# powerBoard.net
KiCad netlist of a schematic drawn in EAGLE
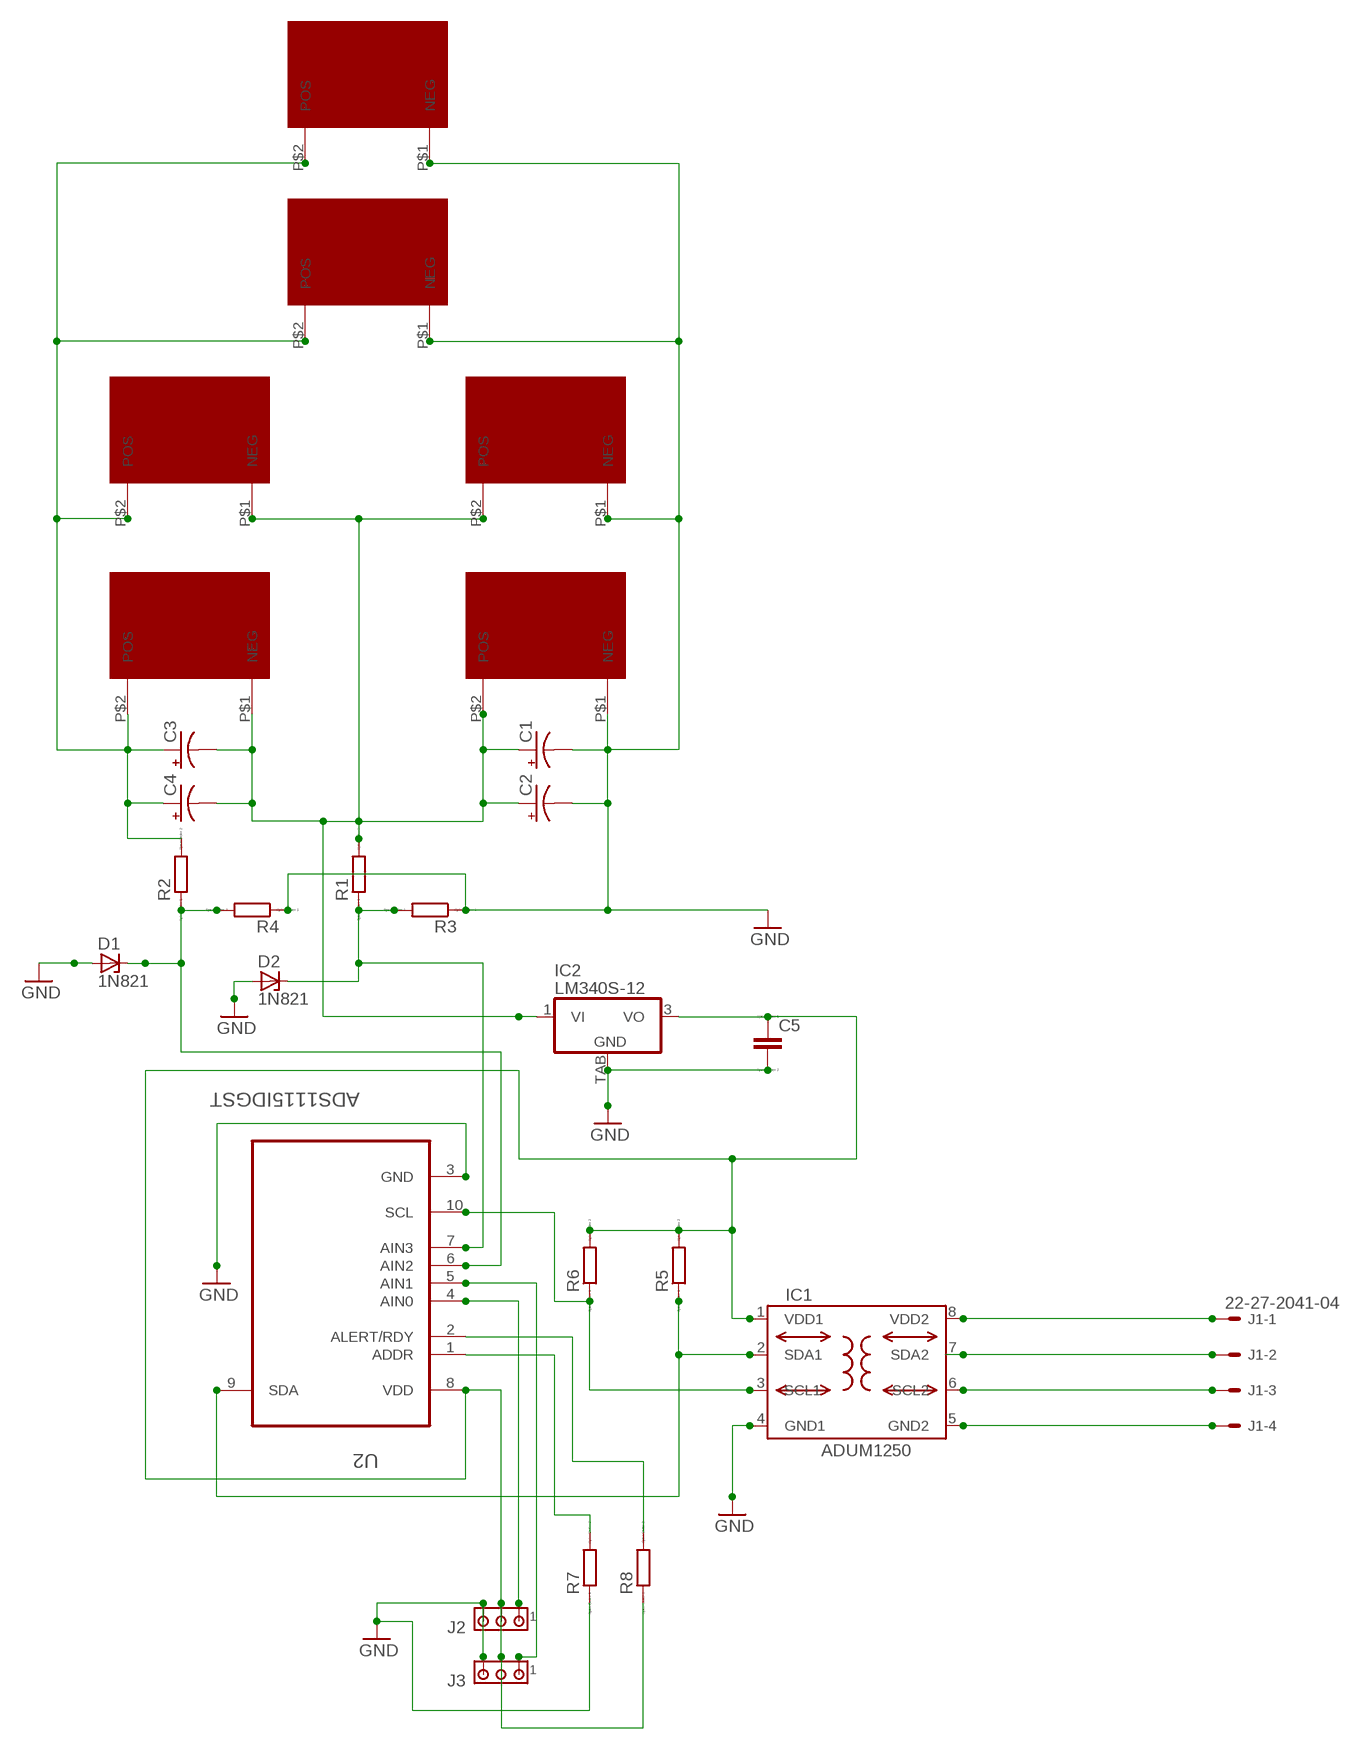
[diagram p0: schematic, sheet 1]

(export (version "E")
  (design (tool "Eeschema 10.0.6"))
  (components
    (comp (ref "C1")
      (value "CPOL-USE7.5-16")
      (footprint "eagle-import:E7,5-16")
      (libsource (lib "eagle-import") (part "CPOL-USE7.5-16"))
    )
    (comp (ref "C2")
      (value "CPOL-USE7.5-16")
      (footprint "eagle-import:E7,5-16")
      (libsource (lib "eagle-import") (part "CPOL-USE7.5-16"))
    )
    (comp (ref "C3")
      (value "CPOL-USE7.5-16")
      (footprint "eagle-import:E7,5-16")
      (libsource (lib "eagle-import") (part "CPOL-USE7.5-16"))
    )
    (comp (ref "C4")
      (value "CPOL-USE7.5-16")
      (footprint "eagle-import:E7,5-16")
      (libsource (lib "eagle-import") (part "CPOL-USE7.5-16"))
    )
    (comp (ref "C5")
      (value "CC2012")
      (footprint "eagle-import:C2012")
      (libsource (lib "eagle-import") (part "CC2012"))
    )
    (comp (ref "D1")
      (value "1N821")
      (footprint "eagle-import:DO35Z10")
      (libsource (lib "eagle-import") (part "1N821"))
    )
    (comp (ref "D2")
      (value "1N821")
      (footprint "eagle-import:DO35Z10")
      (libsource (lib "eagle-import") (part "1N821"))
    )
    (comp (ref "IC1")
      (value "ADUM1250")
      (footprint "eagle-import:SO8-COOL")
      (libsource (lib "eagle-import") (part "ADUM1250"))
    )
    (comp (ref "IC2")
      (value "LM340S-12")
      (footprint "eagle-import:TO263-3")
      (libsource (lib "eagle-import") (part "LM340?-S12"))
    )
    (comp (ref "J1")
      (value "22-27-2041-04")
      (footprint "eagle-import:6410-04")
      (libsource (lib "eagle-import") (part "22-?-0427-2041"))
    )
    (comp (ref "J2")
      (value "MTA03-100")
      (footprint "eagle-import:10X03MTA")
      (libsource (lib "eagle-import") (part "MTA03-100"))
    )
    (comp (ref "J3")
      (value "MTA03-100")
      (footprint "eagle-import:10X03MTA")
      (libsource (lib "eagle-import") (part "MTA03-100"))
    )
    (comp (ref "R1")
      (value "RR1206")
      (footprint "eagle-import:R1206")
      (libsource (lib "eagle-import") (part "RR1206"))
    )
    (comp (ref "R2")
      (value "RR1206")
      (footprint "eagle-import:R1206")
      (libsource (lib "eagle-import") (part "RR1206"))
    )
    (comp (ref "R3")
      (value "RR1206")
      (footprint "eagle-import:R1206")
      (libsource (lib "eagle-import") (part "RR1206"))
    )
    (comp (ref "R4")
      (value "RR1206")
      (footprint "eagle-import:R1206")
      (libsource (lib "eagle-import") (part "RR1206"))
    )
    (comp (ref "R5")
      (value "RR1005")
      (footprint "eagle-import:R1005")
      (libsource (lib "eagle-import") (part "RR1005"))
    )
    (comp (ref "R6")
      (value "RR1005")
      (footprint "eagle-import:R1005")
      (libsource (lib "eagle-import") (part "RR1005"))
    )
    (comp (ref "R7")
      (value "RR1005")
      (footprint "eagle-import:R1005")
      (libsource (lib "eagle-import") (part "RR1005"))
    )
    (comp (ref "R8")
      (value "RR1005")
      (footprint "eagle-import:R1005")
      (libsource (lib "eagle-import") (part "RR1005"))
    )
    (comp (ref "U$1")
      (value "XT60")
      (footprint "eagle-import:XT60")
      (libsource (lib "eagle-import") (part "XT60"))
    )
    (comp (ref "U$2")
      (value "XT60")
      (footprint "eagle-import:XT60")
      (libsource (lib "eagle-import") (part "XT60"))
    )
    (comp (ref "U$3")
      (value "XT60")
      (footprint "eagle-import:XT60")
      (libsource (lib "eagle-import") (part "XT60"))
    )
    (comp (ref "U$4")
      (value "XT60")
      (footprint "eagle-import:XT60")
      (libsource (lib "eagle-import") (part "XT60"))
    )
    (comp (ref "U$5")
      (value "XT60")
      (footprint "eagle-import:XT60")
      (libsource (lib "eagle-import") (part "XT60"))
    )
    (comp (ref "U$6")
      (value "XT60")
      (footprint "eagle-import:XT60")
      (libsource (lib "eagle-import") (part "XT60"))
    )
    (comp (ref "U2")
      (value "ADS1115IDGST")
      (footprint "eagle-import:SOP50P490X110-10N")
      (libsource (lib "eagle-import") (part "ADS1115IDGST"))
    )
  )
  (nets
    (net (code "1") (name "GND") (class "Default")
      (node (ref "C1") (pin "-") (pinfunction "-_-") (pintype "passive"))
      (node (ref "C2") (pin "-") (pinfunction "-_-") (pintype "passive"))
      (node (ref "C5") (pin "2") (pinfunction "2_2") (pintype "passive"))
      (node (ref "D1") (pin "A") (pinfunction "A_A") (pintype "passive"))
      (node (ref "D2") (pin "A") (pinfunction "A_A") (pintype "passive"))
      (node (ref "IC1") (pin "4") (pinfunction "GND1_4") (pintype "power_in"))
      (node (ref "IC2") (pin "TAB") (pinfunction "GND_TAB") (pintype "passive"))
      (node (ref "J2") (pin "3") (pinfunction "3_3") (pintype "passive"))
      (node (ref "J3") (pin "3") (pinfunction "3_3") (pintype "passive"))
      (node (ref "R3") (pin "1") (pinfunction "1_1") (pintype "passive"))
      (node (ref "R4") (pin "1") (pinfunction "1_1") (pintype "passive"))
      (node (ref "R7") (pin "1") (pinfunction "1_1") (pintype "passive"))
      (node (ref "U$1") (pin "P$1") (pinfunction "NEG_P$1") (pintype "power_in"))
      (node (ref "U$4") (pin "P$1") (pinfunction "NEG_P$1") (pintype "power_in"))
      (node (ref "U$5") (pin "P$1") (pinfunction "NEG_P$1") (pintype "power_in"))
      (node (ref "U$6") (pin "P$1") (pinfunction "NEG_P$1") (pintype "power_in"))
      (node (ref "U2") (pin "3") (pinfunction "GND_3") (pintype "passive"))
    )
    (net (code "2") (name "Net-(IC1-GND2)") (class "Default")
      (node (ref "IC1") (pin "5") (pinfunction "GND2_5") (pintype "power_in"))
      (node (ref "J1") (pin "4") (pinfunction "S_4") (pintype "passive"))
    )
    (net (code "3") (name "Net-(IC1-SCL1)") (class "Default")
      (node (ref "IC1") (pin "3") (pinfunction "SCL1_3") (pintype "bidirectional"))
      (node (ref "R6") (pin "1") (pinfunction "1_1") (pintype "passive"))
      (node (ref "U2") (pin "10") (pinfunction "SCL_10") (pintype "input"))
    )
    (net (code "4") (name "Net-(IC1-SCL2)") (class "Default")
      (node (ref "IC1") (pin "6") (pinfunction "SCL2_6") (pintype "bidirectional"))
      (node (ref "J1") (pin "3") (pinfunction "S_3") (pintype "passive"))
    )
    (net (code "5") (name "Net-(IC1-SDA1)") (class "Default")
      (node (ref "IC1") (pin "2") (pinfunction "SDA1_2") (pintype "bidirectional"))
      (node (ref "R5") (pin "1") (pinfunction "1_1") (pintype "passive"))
      (node (ref "U2") (pin "9") (pinfunction "SDA_9") (pintype "bidirectional"))
    )
    (net (code "6") (name "Net-(IC1-SDA2)") (class "Default")
      (node (ref "IC1") (pin "7") (pinfunction "SDA2_7") (pintype "bidirectional"))
      (node (ref "J1") (pin "2") (pinfunction "S_2") (pintype "passive"))
    )
    (net (code "7") (name "Net-(IC1-VDD1)") (class "Default")
      (node (ref "C5") (pin "1") (pinfunction "1_1") (pintype "passive"))
      (node (ref "IC1") (pin "1") (pinfunction "VDD1_1") (pintype "power_in"))
      (node (ref "IC2") (pin "3") (pinfunction "VO_3") (pintype "passive"))
      (node (ref "J2") (pin "2") (pinfunction "2_2") (pintype "passive"))
      (node (ref "J3") (pin "2") (pinfunction "2_2") (pintype "passive"))
      (node (ref "R5") (pin "2") (pinfunction "2_2") (pintype "passive"))
      (node (ref "R6") (pin "2") (pinfunction "2_2") (pintype "passive"))
      (node (ref "R8") (pin "1") (pinfunction "1_1") (pintype "passive"))
      (node (ref "U2") (pin "8") (pinfunction "VDD_8") (pintype "power_in"))
    )
    (net (code "8") (name "Net-(IC1-VDD2)") (class "Default")
      (node (ref "IC1") (pin "8") (pinfunction "VDD2_8") (pintype "power_in"))
      (node (ref "J1") (pin "1") (pinfunction "S_1") (pintype "passive"))
    )
    (net (code "9") (name "Net-(IC2-VI)") (class "Default")
      (node (ref "C1") (pin "+") (pinfunction "+_+") (pintype "passive"))
      (node (ref "C2") (pin "+") (pinfunction "+_+") (pintype "passive"))
      (node (ref "C3") (pin "-") (pinfunction "-_-") (pintype "passive"))
      (node (ref "C4") (pin "-") (pinfunction "-_-") (pintype "passive"))
      (node (ref "IC2") (pin "1") (pinfunction "VI_1") (pintype "input"))
      (node (ref "R1") (pin "2") (pinfunction "2_2") (pintype "passive"))
      (node (ref "U$1") (pin "P$2") (pinfunction "POS_P$2") (pintype "power_in"))
      (node (ref "U$2") (pin "P$1") (pinfunction "NEG_P$1") (pintype "power_in"))
      (node (ref "U$3") (pin "P$1") (pinfunction "NEG_P$1") (pintype "power_in"))
      (node (ref "U$4") (pin "P$2") (pinfunction "POS_P$2") (pintype "power_in"))
    )
    (net (code "10") (name "Net-(U$2-POS)") (class "Default")
      (node (ref "C3") (pin "+") (pinfunction "+_+") (pintype "passive"))
      (node (ref "C4") (pin "+") (pinfunction "+_+") (pintype "passive"))
      (node (ref "R2") (pin "2") (pinfunction "2_2") (pintype "passive"))
      (node (ref "U$2") (pin "P$2") (pinfunction "POS_P$2") (pintype "power_in"))
      (node (ref "U$3") (pin "P$2") (pinfunction "POS_P$2") (pintype "power_in"))
      (node (ref "U$5") (pin "P$2") (pinfunction "POS_P$2") (pintype "power_in"))
      (node (ref "U$6") (pin "P$2") (pinfunction "POS_P$2") (pintype "power_in"))
    )
    (net (code "11") (name "Net-(U2-ADDR)") (class "Default")
      (node (ref "R7") (pin "2") (pinfunction "2_2") (pintype "passive"))
      (node (ref "U2") (pin "1") (pinfunction "ADDR_1") (pintype "input"))
    )
    (net (code "12") (name "Net-(U2-AIN0)") (class "Default")
      (node (ref "J2") (pin "1") (pinfunction "1_1") (pintype "passive"))
      (node (ref "U2") (pin "4") (pinfunction "AIN0_4") (pintype "input"))
    )
    (net (code "13") (name "Net-(U2-AIN1)") (class "Default")
      (node (ref "J3") (pin "1") (pinfunction "1_1") (pintype "passive"))
      (node (ref "U2") (pin "5") (pinfunction "AIN1_5") (pintype "input"))
    )
    (net (code "14") (name "Net-(U2-AIN2)") (class "Default")
      (node (ref "D1") (pin "C") (pinfunction "C_C") (pintype "passive"))
      (node (ref "R2") (pin "1") (pinfunction "1_1") (pintype "passive"))
      (node (ref "R4") (pin "2") (pinfunction "2_2") (pintype "passive"))
      (node (ref "U2") (pin "6") (pinfunction "AIN2_6") (pintype "input"))
    )
    (net (code "15") (name "Net-(U2-AIN3)") (class "Default")
      (node (ref "D2") (pin "C") (pinfunction "C_C") (pintype "passive"))
      (node (ref "R1") (pin "1") (pinfunction "1_1") (pintype "passive"))
      (node (ref "R3") (pin "2") (pinfunction "2_2") (pintype "passive"))
      (node (ref "U2") (pin "7") (pinfunction "AIN3_7") (pintype "input"))
    )
    (net (code "16") (name "Net-(U2-ALERT{slash}RDY)") (class "Default")
      (node (ref "R8") (pin "2") (pinfunction "2_2") (pintype "passive"))
      (node (ref "U2") (pin "2") (pinfunction "ALERT/RDY_2") (pintype "input"))
    )
  )
)
